# Buzzer.net
KiCad netlist of a schematic drawn in Altium Designer
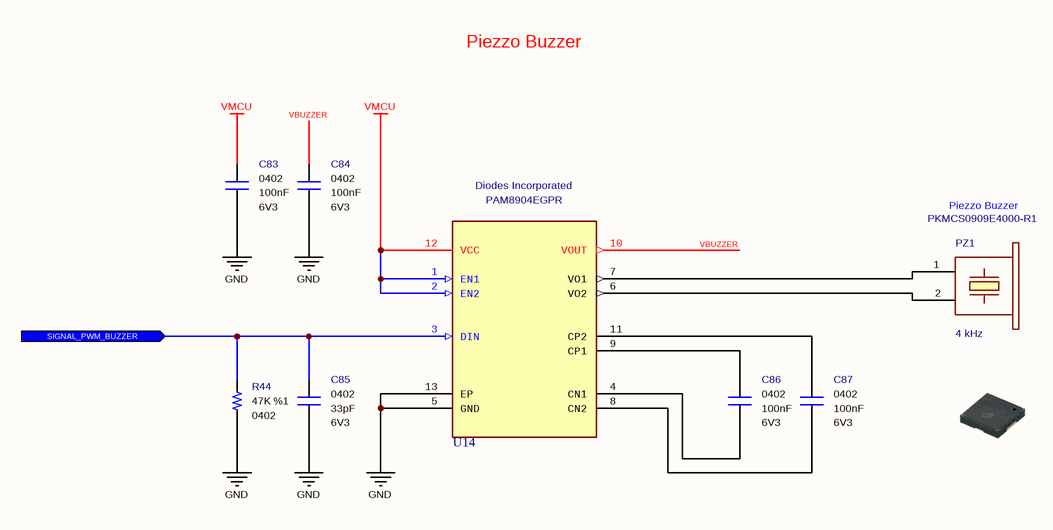
[diagram p0: Buzzer.SchDoc]

(export (version "E")
  (design (tool "Eeschema 10.0.6"))
  (components
    (comp (ref "C83")
      (value "100nF")
      (footprint "CAPACITOR_0402")
      (description "Capacitor - 100nF [0402-6V3] (Ceramic)")
      (fields
        (field (name "TOLERANCE") "%10")
        (field (name "CASE") "0402")
        (field (name "VOLTAGE") "6V3")
        (field (name "MANUFACTURER PART NUMBER") "04026D104KAT4A")
      )
      (libsource (lib "Ovoo_Library") (part "Capacitor - 100nF [0402-6V3]"))
    )
    (comp (ref "C84")
      (value "100nF")
      (footprint "CAPACITOR_0402")
      (description "Capacitor - 100nF [0402-6V3] (Ceramic)")
      (fields
        (field (name "TOLERANCE") "%10")
        (field (name "CASE") "0402")
        (field (name "VOLTAGE") "6V3")
        (field (name "MANUFACTURER PART NUMBER") "04026D104KAT4A")
      )
      (libsource (lib "Ovoo_Library") (part "Capacitor - 100nF [0402-6V3]"))
    )
    (comp (ref "C85")
      (value "33pF")
      (footprint "CAPACITOR_0402")
      (description "Capacitor - 33pF [0402] (Ceramic)")
      (fields
        (field (name "TOLERANCE") "10%")
        (field (name "CASE") "0402")
        (field (name "VOLTAGE") "6V3")
        (field (name "MANUFACTURER PART NUMBER") "C0402C330J9RACAUTO")
      )
      (libsource (lib "Ovoo_Library") (part "Capacitor - 33pF [0402-6V3]"))
    )
    (comp (ref "C86")
      (value "100nF")
      (footprint "CAPACITOR_0402")
      (description "Capacitor - 100nF [0402-6V3] (Ceramic)")
      (fields
        (field (name "TOLERANCE") "%10")
        (field (name "CASE") "0402")
        (field (name "VOLTAGE") "6V3")
        (field (name "MANUFACTURER PART NUMBER") "04026D104KAT4A")
      )
      (libsource (lib "Ovoo_Library") (part "Capacitor - 100nF [0402-6V3]"))
    )
    (comp (ref "C87")
      (value "100nF")
      (footprint "CAPACITOR_0402")
      (description "Capacitor - 100nF [0402-6V3] (Ceramic)")
      (fields
        (field (name "TOLERANCE") "%10")
        (field (name "CASE") "0402")
        (field (name "VOLTAGE") "6V3")
        (field (name "MANUFACTURER PART NUMBER") "04026D104KAT4A")
      )
      (libsource (lib "Ovoo_Library") (part "Capacitor - 100nF [0402-6V3]"))
    )
    (comp (ref "PZ1")
      (value "Piezo Buzzers & Audio Indicators")
      (footprint "Murata Piezzo Buzzer")
      (description "Piezo Buzzers & Audio Indicators Piezo Buzzer 9x9mm 4KHz 1.9mm Thickness")
      (fields
        (field (name "FREQUENCY") "4 kHz")
        (field (name "MOUSER PART NUMBER") "81-PKMCS0909E4000-R1")
        (field (name "MANUFACTURER PART NUMBER") "PKMCS0909E4000-R1")
        (field (name "DEVICE TYPE") "Piezzo Buzzer")
      )
      (libsource (lib "Ovoo_Library") (part "Buzzer - PKMCS0909E4000-R1"))
    )
    (comp (ref "R44")
      (value "47K")
      (footprint "RESISTOR_0402")
      (description "Thick Film Resistors - SMD 1/16 W 47 Kohms 1%")
      (fields
        (field (name "TOLERANCE") "%1")
        (field (name "CASE") "0402")
        (field (name "MANUFACTURER PART NUMBER") "CRCW040247K0FKED")
        (field (name "MOUSER PART NUMBER") "71-CRCW0402-47K-E3")
      )
      (libsource (lib "Ovoo_Library") (part "Resistor - 47K"))
    )
    (comp (ref "U14")
      (value "Audio Amplifiers")
      (footprint "QFN2020-12")
      (description "Audio Amplifiers Audio High Volt")
      (fields
        (field (name "MOUSER PART NUMBER") "621-PAM8904EGPR")
        (field (name "MANUFACTURER NAME") "Diodes Incorporated")
        (field (name "MANUFACTURER PART NUMBER") "PAM8904EGPR")
      )
      (libsource (lib "Ovoo_Library") (part "IC - PAM8904EGPR"))
    )
  )
  (nets
    (net (code "1") (name "/SIGNAL_PWM_BUZZER") (class "Default")
      (node (ref "C85") (pin "2") (pinfunction "2_2") (pintype "passive"))
      (node (ref "R44") (pin "2") (pinfunction "2_2") (pintype "passive"))
      (node (ref "U14") (pin "3") (pinfunction "DIN_3") (pintype "input"))
    )
    (net (code "2") (name "/VBUZZER") (class "Default")
      (node (ref "C84") (pin "2") (pinfunction "2_2") (pintype "passive"))
      (node (ref "U14") (pin "10") (pinfunction "VOUT_10") (pintype "output"))
    )
    (net (code "3") (name "GND") (class "Default")
      (node (ref "C83") (pin "1") (pinfunction "1_1") (pintype "passive"))
      (node (ref "C84") (pin "1") (pinfunction "1_1") (pintype "passive"))
      (node (ref "C85") (pin "1") (pinfunction "1_1") (pintype "passive"))
      (node (ref "R44") (pin "1") (pinfunction "1_1") (pintype "passive"))
      (node (ref "U14") (pin "13") (pinfunction "EP_13") (pintype "passive"))
      (node (ref "U14") (pin "5") (pinfunction "GND_5") (pintype "passive"))
    )
    (net (code "4") (name "Net-(PZ1-+)") (class "Default")
      (node (ref "PZ1") (pin "1") (pinfunction "+_1") (pintype "passive"))
      (node (ref "U14") (pin "7") (pinfunction "VO1_7") (pintype "output"))
    )
    (net (code "5") (name "Net-(PZ1--)") (class "Default")
      (node (ref "PZ1") (pin "2") (pinfunction "-_2") (pintype "passive"))
      (node (ref "U14") (pin "6") (pinfunction "VO2_6") (pintype "output"))
    )
    (net (code "6") (name "Net-(U14-CN1)") (class "Default")
      (node (ref "C86") (pin "1") (pinfunction "1_1") (pintype "passive"))
      (node (ref "U14") (pin "4") (pinfunction "CN1_4") (pintype "passive"))
    )
    (net (code "7") (name "Net-(U14-CN2)") (class "Default")
      (node (ref "C87") (pin "1") (pinfunction "1_1") (pintype "passive"))
      (node (ref "U14") (pin "8") (pinfunction "CN2_8") (pintype "passive"))
    )
    (net (code "8") (name "Net-(U14-CP1)") (class "Default")
      (node (ref "C86") (pin "2") (pinfunction "2_2") (pintype "passive"))
      (node (ref "U14") (pin "9") (pinfunction "CP1_9") (pintype "passive"))
    )
    (net (code "9") (name "Net-(U14-CP2)") (class "Default")
      (node (ref "C87") (pin "2") (pinfunction "2_2") (pintype "passive"))
      (node (ref "U14") (pin "11") (pinfunction "CP2_11") (pintype "passive"))
    )
    (net (code "10") (name "VMCU") (class "Default")
      (node (ref "C83") (pin "2") (pinfunction "2_2") (pintype "passive"))
      (node (ref "U14") (pin "1") (pinfunction "EN1_1") (pintype "input"))
      (node (ref "U14") (pin "12") (pinfunction "VCC_12") (pintype "power_in"))
      (node (ref "U14") (pin "2") (pinfunction "EN2_2") (pintype "input"))
    )
  )
)
